# somfyOw_shape_v2.net
KiCad netlist of a schematic drawn in EAGLE
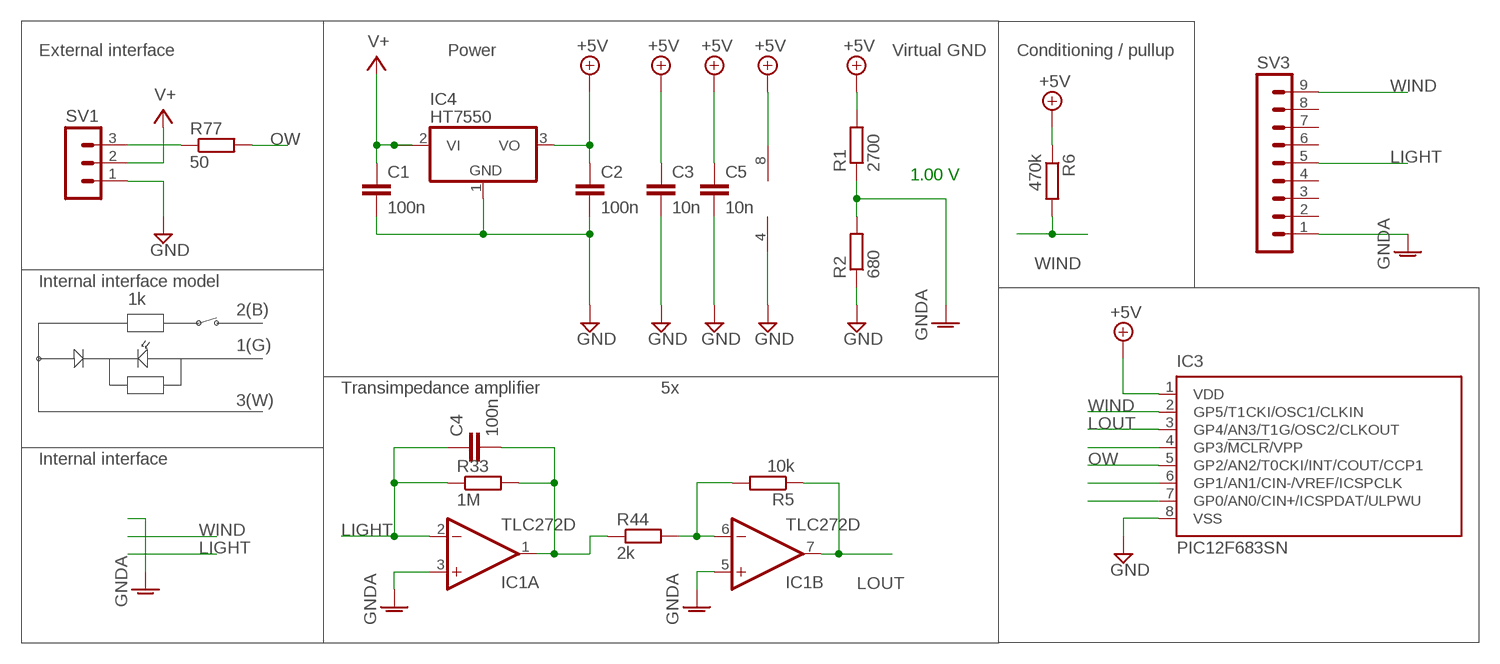
[diagram p0: schematic, sheet 1]

(export (version "E")
  (design (tool "Eeschema 10.0.6"))
  (components
    (comp (ref "C1")
      (value "100n")
      (footprint "eagle-import:C1206")
      (libsource (lib "eagle-import") (part "C-EUC1206"))
    )
    (comp (ref "C2")
      (value "100n")
      (footprint "eagle-import:C1206")
      (libsource (lib "eagle-import") (part "C-EUC1206"))
    )
    (comp (ref "C3")
      (value "10n")
      (footprint "eagle-import:C1206")
      (libsource (lib "eagle-import") (part "C-EUC1206"))
    )
    (comp (ref "C4")
      (value "100n")
      (footprint "eagle-import:C1206")
      (libsource (lib "eagle-import") (part "C-EUC1206"))
    )
    (comp (ref "C5")
      (value "10n")
      (footprint "eagle-import:C1206")
      (libsource (lib "eagle-import") (part "C-EUC1206"))
    )
    (comp (ref "IC1")
      (value "TLC272D")
      (footprint "eagle-import:SO08")
      (libsource (lib "eagle-import") (part "TLC272D"))
    )
    (comp (ref "IC3")
      (value "PIC12F683SN")
      (footprint "eagle-import:SO-08")
      (fields (field (name "MF") "MICROCHIP") (field (name "MPN") "PIC12F683-I/SN"))
      (libsource (lib "eagle-import") (part "PIC12F683SN"))
    )
    (comp (ref "IC4")
      (value "HT7550")
      (footprint "eagle-import:SOT89")
      (libsource (lib "eagle-import") (part "MCP1703MB12"))
    )
    (comp (ref "R1")
      (value "2700")
      (footprint "eagle-import:M1206")
      (libsource (lib "eagle-import") (part "R-EU_M1206"))
    )
    (comp (ref "R2")
      (value "680")
      (footprint "eagle-import:M1206")
      (libsource (lib "eagle-import") (part "R-EU_M1206"))
    )
    (comp (ref "R5")
      (value "10k")
      (footprint "eagle-import:M1206")
      (libsource (lib "eagle-import") (part "R-EU_M1206"))
    )
    (comp (ref "R6")
      (value "470k")
      (footprint "eagle-import:M1206")
      (libsource (lib "eagle-import") (part "R-EU_M1206"))
    )
    (comp (ref "R33")
      (value "1M")
      (footprint "eagle-import:R1206")
      (libsource (lib "eagle-import") (part "R-EU_R1206"))
    )
    (comp (ref "R44")
      (value "2k")
      (footprint "eagle-import:R1206")
      (libsource (lib "eagle-import") (part "R-EU_R1206"))
    )
    (comp (ref "R77")
      (value "50")
      (footprint "eagle-import:R1206")
      (libsource (lib "eagle-import") (part "R-EU_R1206"))
    )
    (comp (ref "SV1")
      (value "MA03-1")
      (footprint "eagle-import:MA03-1")
      (libsource (lib "eagle-import") (part "MA03-1"))
    )
    (comp (ref "SV3")
      (value "MA09-1W")
      (footprint "eagle-import:MA09-1W")
      (libsource (lib "eagle-import") (part "MA09-1W"))
    )
  )
  (nets
    (net (code "1") (name "+5V") (class "Default")
      (node (ref "C2") (pin "1") (pinfunction "1_1") (pintype "passive"))
      (node (ref "C3") (pin "1") (pinfunction "1_1") (pintype "passive"))
      (node (ref "C5") (pin "1") (pinfunction "1_1") (pintype "passive"))
      (node (ref "IC1") (pin "8") (pinfunction "V+_8") (pintype "power_in"))
      (node (ref "IC3") (pin "1") (pinfunction "VDD_1") (pintype "power_in"))
      (node (ref "IC4") (pin "3") (pinfunction "VO_3") (pintype "passive"))
      (node (ref "R1") (pin "2") (pinfunction "2_2") (pintype "passive"))
      (node (ref "R6") (pin "1") (pinfunction "1_1") (pintype "passive"))
    )
    (net (code "2") (name "/LIGHT") (class "Default")
      (node (ref "C4") (pin "1") (pinfunction "1_1") (pintype "passive"))
      (node (ref "IC1") (pin "2") (pinfunction "-IN_2") (pintype "input"))
      (node (ref "R33") (pin "1") (pinfunction "1_1") (pintype "passive"))
      (node (ref "SV3") (pin "5") (pinfunction "5_5") (pintype "passive"))
    )
    (net (code "3") (name "/LOUT") (class "Default")
      (node (ref "IC1") (pin "7") (pinfunction "OUT_7") (pintype "output"))
      (node (ref "IC3") (pin "3") (pinfunction "GP4/AN3/T1G/OSC2/CLKOUT_3") (pintype "bidirectional"))
      (node (ref "R5") (pin "1") (pinfunction "1_1") (pintype "passive"))
    )
    (net (code "4") (name "/OW") (class "Default")
      (node (ref "IC3") (pin "5") (pinfunction "GP2/AN2/T0CKI/INT/COUT/CCP1_5") (pintype "bidirectional"))
      (node (ref "R77") (pin "2") (pinfunction "2_2") (pintype "passive"))
    )
    (net (code "5") (name "/WIND") (class "Default")
      (node (ref "IC3") (pin "2") (pinfunction "GP5/T1CKI/OSC1/CLKIN_2") (pintype "bidirectional"))
      (node (ref "R6") (pin "2") (pinfunction "2_2") (pintype "passive"))
      (node (ref "SV3") (pin "9") (pinfunction "9_9") (pintype "passive"))
    )
    (net (code "6") (name "GND") (class "Default")
      (node (ref "C1") (pin "2") (pinfunction "2_2") (pintype "passive"))
      (node (ref "C2") (pin "2") (pinfunction "2_2") (pintype "passive"))
      (node (ref "C3") (pin "2") (pinfunction "2_2") (pintype "passive"))
      (node (ref "C5") (pin "2") (pinfunction "2_2") (pintype "passive"))
      (node (ref "IC1") (pin "4") (pinfunction "V-_4") (pintype "power_in"))
      (node (ref "IC3") (pin "8") (pinfunction "VSS_8") (pintype "power_in"))
      (node (ref "IC4") (pin "1") (pinfunction "GND_1") (pintype "passive"))
      (node (ref "R2") (pin "1") (pinfunction "1_1") (pintype "passive"))
      (node (ref "SV1") (pin "1") (pinfunction "1_1") (pintype "passive"))
    )
    (net (code "7") (name "GNDA") (class "Default")
      (node (ref "IC1") (pin "3") (pinfunction "+IN_3") (pintype "input"))
      (node (ref "IC1") (pin "5") (pinfunction "+IN_5") (pintype "input"))
      (node (ref "R1") (pin "1") (pinfunction "1_1") (pintype "passive"))
      (node (ref "R2") (pin "2") (pinfunction "2_2") (pintype "passive"))
      (node (ref "SV3") (pin "1") (pinfunction "1_1") (pintype "passive"))
    )
    (net (code "8") (name "Net-(IC1A-OUT)") (class "Default")
      (node (ref "C4") (pin "2") (pinfunction "2_2") (pintype "passive"))
      (node (ref "IC1") (pin "1") (pinfunction "OUT_1") (pintype "output"))
      (node (ref "R33") (pin "2") (pinfunction "2_2") (pintype "passive"))
      (node (ref "R44") (pin "1") (pinfunction "1_1") (pintype "passive"))
    )
    (net (code "9") (name "Net-(IC1B--IN)") (class "Default")
      (node (ref "IC1") (pin "6") (pinfunction "-IN_6") (pintype "input"))
      (node (ref "R44") (pin "2") (pinfunction "2_2") (pintype "passive"))
      (node (ref "R5") (pin "2") (pinfunction "2_2") (pintype "passive"))
    )
    (net (code "10") (name "Net-(R77-Pad1)") (class "Default")
      (node (ref "R77") (pin "1") (pinfunction "1_1") (pintype "passive"))
      (node (ref "SV1") (pin "3") (pinfunction "3_3") (pintype "passive"))
    )
    (net (code "11") (name "V+") (class "Default")
      (node (ref "C1") (pin "1") (pinfunction "1_1") (pintype "passive"))
      (node (ref "IC4") (pin "2") (pinfunction "VI_2") (pintype "input"))
      (node (ref "IC4") (pin "2@1") (pinfunction "VI1_2@1") (pintype "input"))
      (node (ref "SV1") (pin "2") (pinfunction "2_2") (pintype "passive"))
    )
    (net (code "12") (name "unconnected-(IC3-GP0{slash}AN0{slash}CIN+{slash}ICSPDAT{slash}ULPWU-Pad7)") (class "Default")
      (node (ref "IC3") (pin "7") (pinfunction "GP0/AN0/CIN+/ICSPDAT/ULPWU_7") (pintype "bidirectional"))
    )
    (net (code "13") (name "unconnected-(IC3-GP1{slash}AN1{slash}CIN-{slash}VREF{slash}ICSPCLK-Pad6)") (class "Default")
      (node (ref "IC3") (pin "6") (pinfunction "GP1/AN1/CIN-/VREF/ICSPCLK_6") (pintype "bidirectional"))
    )
    (net (code "14") (name "unconnected-(IC3-GP3{slash}~{MCLR}{slash}VPP-Pad4)") (class "Default")
      (node (ref "IC3") (pin "4") (pinfunction "GP3/~{MCLR}/VPP_4") (pintype "bidirectional"))
    )
    (net (code "15") (name "unconnected-(SV3-Pad2)") (class "Default")
      (node (ref "SV3") (pin "2") (pinfunction "2_2") (pintype "passive"))
    )
    (net (code "16") (name "unconnected-(SV3-Pad3)") (class "Default")
      (node (ref "SV3") (pin "3") (pinfunction "3_3") (pintype "passive"))
    )
    (net (code "17") (name "unconnected-(SV3-Pad4)") (class "Default")
      (node (ref "SV3") (pin "4") (pinfunction "4_4") (pintype "passive"))
    )
    (net (code "18") (name "unconnected-(SV3-Pad6)") (class "Default")
      (node (ref "SV3") (pin "6") (pinfunction "6_6") (pintype "passive"))
    )
    (net (code "19") (name "unconnected-(SV3-Pad7)") (class "Default")
      (node (ref "SV3") (pin "7") (pinfunction "7_7") (pintype "passive"))
    )
    (net (code "20") (name "unconnected-(SV3-Pad8)") (class "Default")
      (node (ref "SV3") (pin "8") (pinfunction "8_8") (pintype "passive"))
    )
  )
)
